# SCH_HVACPCBProject_2026-05-03.net
KiCad netlist of a schematic drawn in EasyEDA
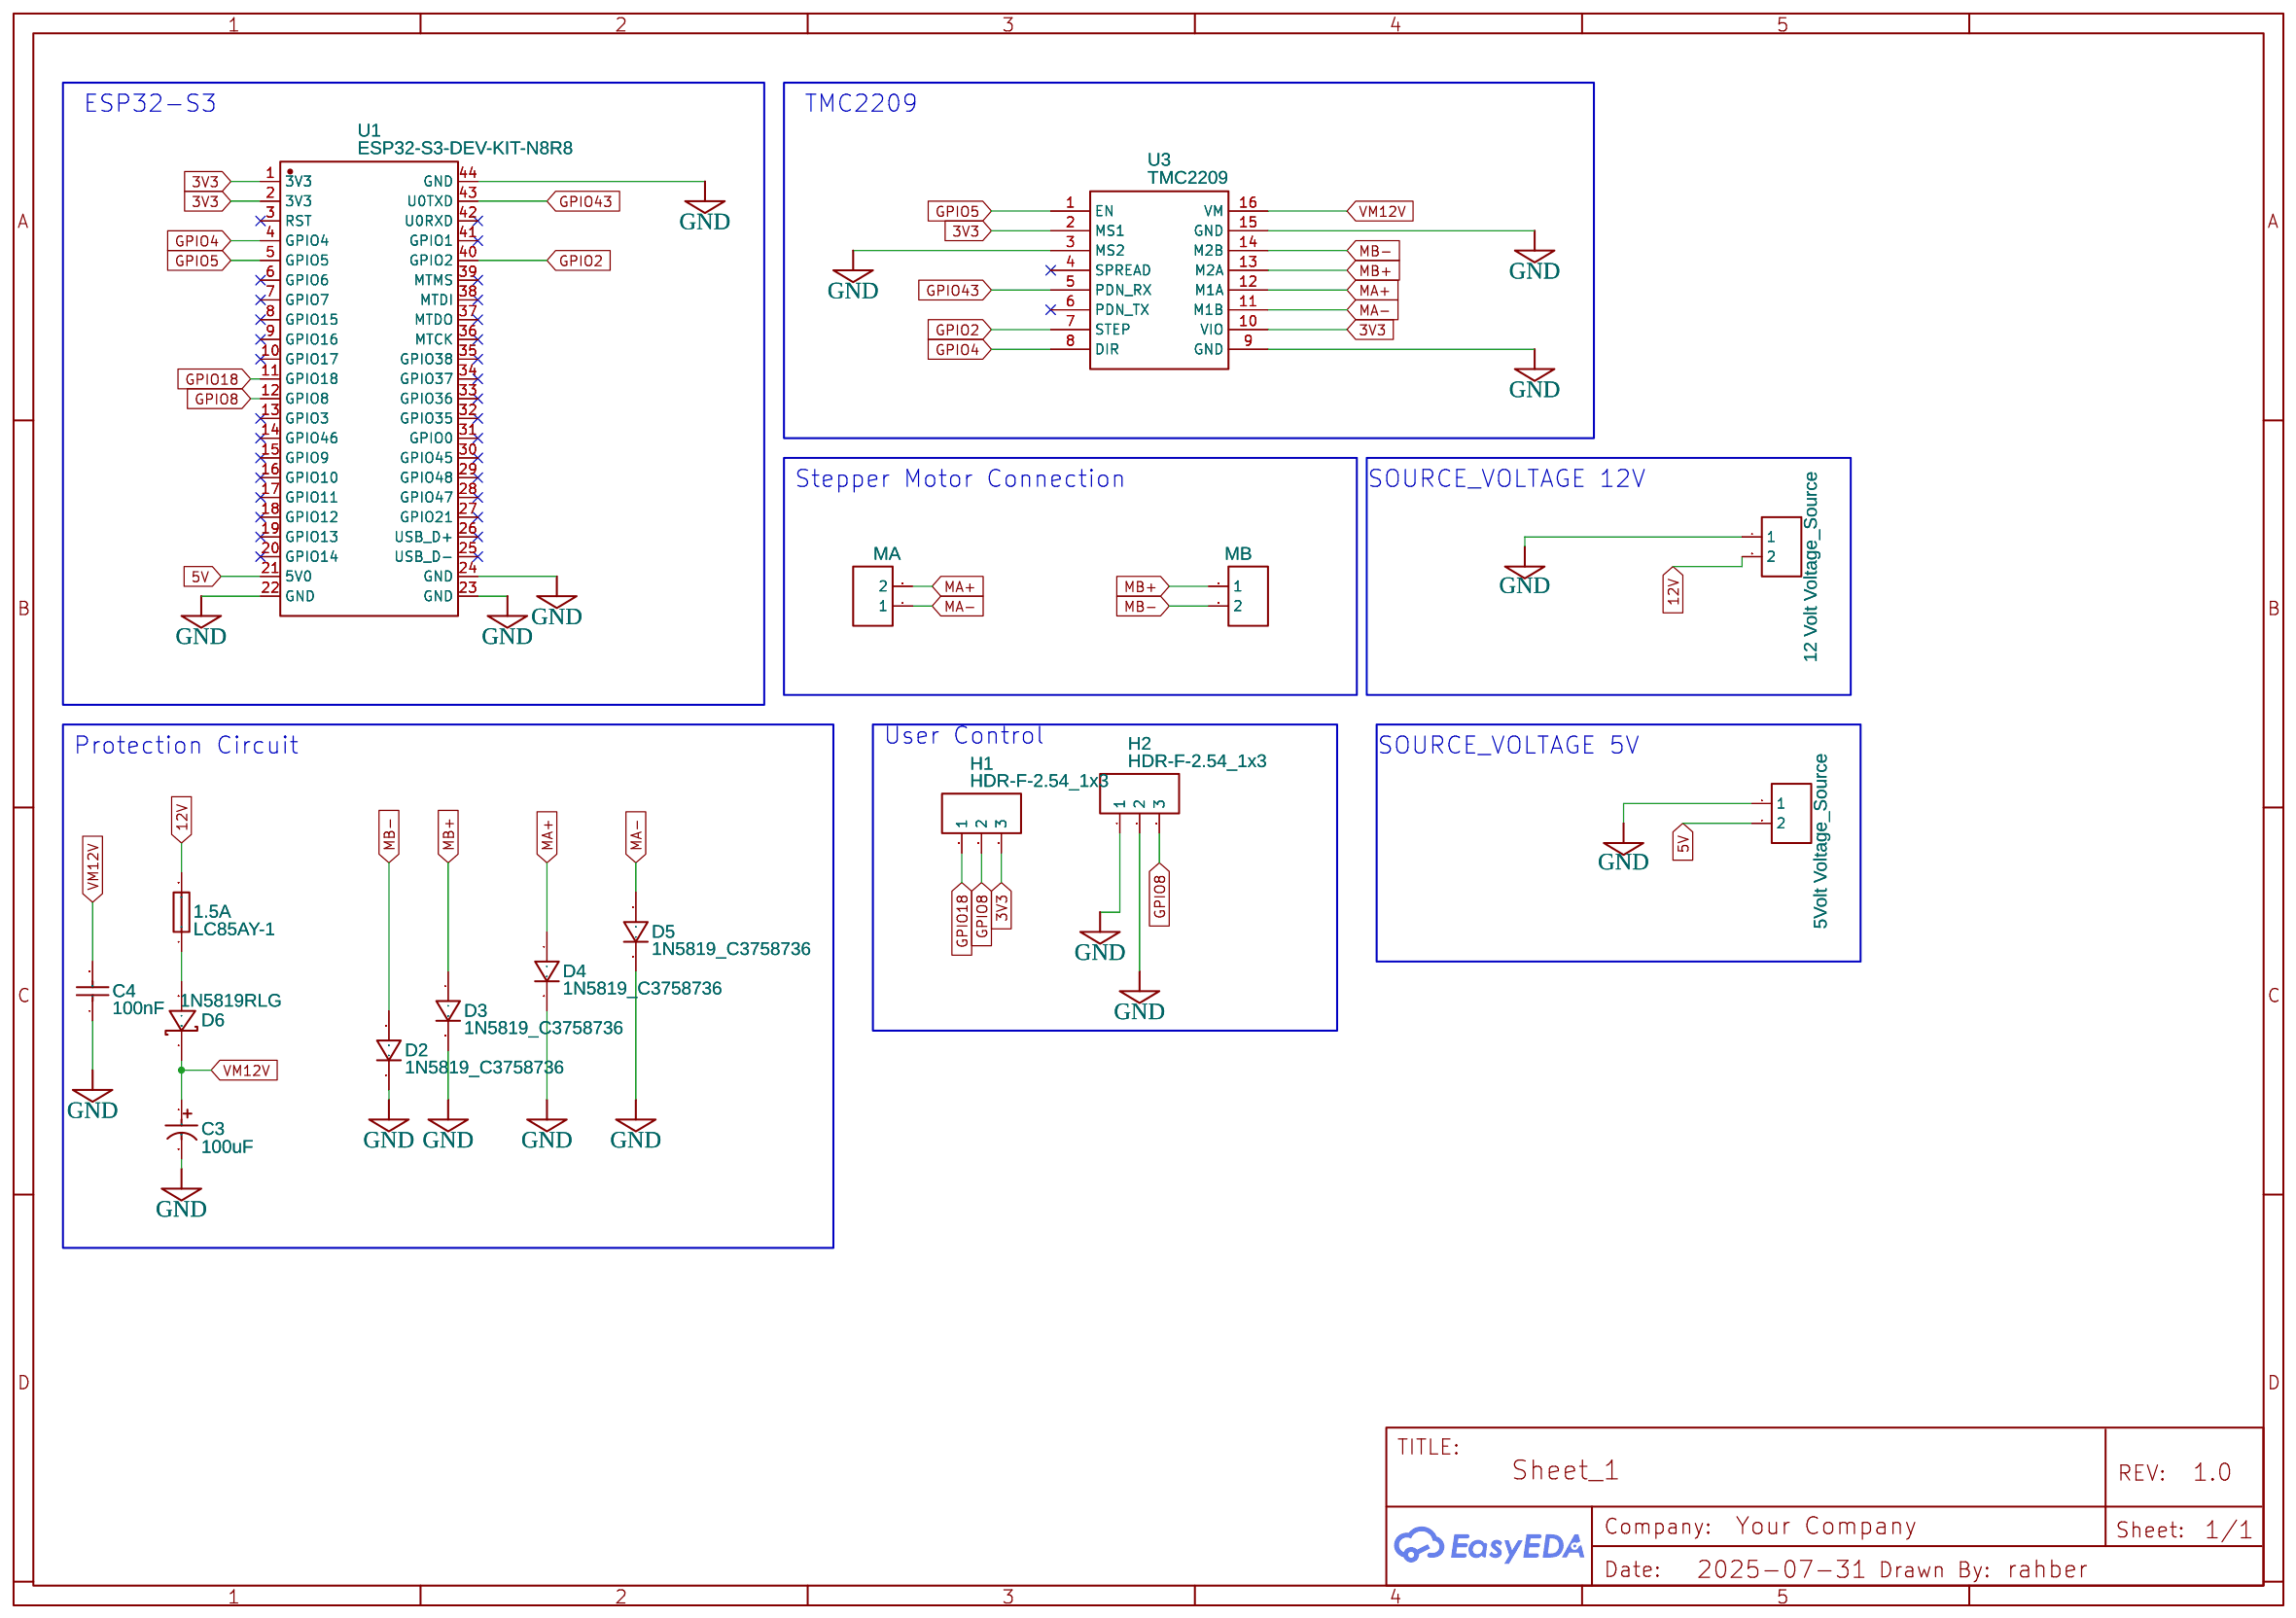
[diagram p0: schematic sheet]

(export (version "E")
  (design (tool "Eeschema 10.0.6"))
  (components
    (comp (ref "1.5A")
      (value "LC85AY-1")
      (fields (field (name "Manufacturer") "BOURNS"))
      (libsource (lib "") (part "LC85AY-1"))
    )
    (comp (ref "C3")
      (value "100uF")
      (fields
        (field (name "Manufacturer Part") "NP106V100G12RR0VH2FP0")
        (field (name "Manufacturer") "CX(承兴)")
      )
      (libsource (lib "") (part "Non - polar electrolytic capacitors10uf 100v"))
    )
    (comp (ref "C4")
      (value "100nF")
      (fields (field (name "Manufacturer Part") "瓷片电容47PF 3KV"))
      (libsource (lib "") (part "Ceramic capacitors47PF 3KV"))
    )
    (comp (ref "D2")
      (value "1N5819_C3758736")
      (fields
        (field (name "Manufacturer Part") "1N5819")
        (field (name "Manufacturer") "Taiwan Semiconductor(台湾半导体)")
      )
      (libsource (lib "") (part "1N5819_C3758736"))
    )
    (comp (ref "D3")
      (value "1N5819_C3758736")
      (fields
        (field (name "Manufacturer Part") "1N5819")
        (field (name "Manufacturer") "Taiwan Semiconductor(台湾半导体)")
      )
      (libsource (lib "") (part "1N5819_C3758736"))
    )
    (comp (ref "D4")
      (value "1N5819_C3758736")
      (fields
        (field (name "Manufacturer Part") "1N5819")
        (field (name "Manufacturer") "Taiwan Semiconductor(台湾半导体)")
      )
      (libsource (lib "") (part "1N5819_C3758736"))
    )
    (comp (ref "D5")
      (value "1N5819_C3758736")
      (fields
        (field (name "Manufacturer Part") "1N5819")
        (field (name "Manufacturer") "Taiwan Semiconductor(台湾半导体)")
      )
      (libsource (lib "") (part "1N5819_C3758736"))
    )
    (comp (ref "D6")
      (value "1N5819RLG")
      (fields (field (name "Manufacturer") "onsemi(安森美)"))
      (libsource (lib "") (part "1N5819RLG"))
    )
    (comp (ref "H1") (value "HDR-F-2.54_1x3") (libsource (lib "") (part "HDR-F-2.54_1x3")))
    (comp (ref "H2") (value "HDR-F-2.54_1x3") (libsource (lib "") (part "HDR-F-2.54_1x3")))
    (comp (ref "P1") (value "MB") (libsource (lib "") (part "CONN-TH_2P-P5.08")))
    (comp (ref "P2") (value "MA") (libsource (lib "") (part "CONN-TH_2P-P5.08_1")))
    (comp (ref "P3") (value "12 Volt Voltage_Source") (libsource (lib "") (part "CONN-TH_2P-P5.08")))
    (comp (ref "P5") (value "5Volt Voltage_Source") (libsource (lib "") (part "CONN-TH_2P-P5.08")))
    (comp (ref "U1") (value "ESP32-S3-DEV-KIT-N8R8") (libsource (lib "") (part "ESP32-S3-DEV-KIT-N8R8")))
    (comp (ref "U3") (value "TMC2209") (libsource (lib "") (part "TMC2209")))
  )
  (nets
    (net (code "1") (name "3V3") (class "Default")
      (node (ref "H1") (pin "3") (pinfunction "3_3") (pintype "input"))
      (node (ref "U1") (pin "1") (pinfunction "3V3_1") (pintype "unspecified"))
      (node (ref "U1") (pin "2") (pinfunction "3V3_2") (pintype "unspecified"))
      (node (ref "U3") (pin "10") (pinfunction "VIO_10") (pintype "unspecified"))
      (node (ref "U3") (pin "2") (pinfunction "MS1_2") (pintype "unspecified"))
    )
    (net (code "2") (name "5V") (class "Default")
      (node (ref "P5") (pin "2") (pinfunction "2_2") (pintype "unspecified"))
      (node (ref "U1") (pin "21") (pinfunction "5V0_21") (pintype "unspecified"))
    )
    (net (code "3") (name "12V") (class "Default")
      (node (ref "1.5A") (pin "2") (pinfunction "2_2") (pintype "unspecified"))
      (node (ref "P3") (pin "2") (pinfunction "2_2") (pintype "unspecified"))
    )
    (net (code "4") (name "GND") (class "Default")
      (node (ref "C3") (pin "2") (pinfunction "2_2") (pintype "input"))
      (node (ref "C4") (pin "1") (pinfunction "1_1") (pintype "input"))
      (node (ref "D2") (pin "2") (pinfunction "K_2") (pintype "unspecified"))
      (node (ref "D3") (pin "2") (pinfunction "K_2") (pintype "unspecified"))
      (node (ref "D4") (pin "2") (pinfunction "K_2") (pintype "unspecified"))
      (node (ref "D5") (pin "2") (pinfunction "K_2") (pintype "unspecified"))
      (node (ref "H2") (pin "1") (pinfunction "1_1") (pintype "input"))
      (node (ref "H2") (pin "2") (pinfunction "2_2") (pintype "input"))
      (node (ref "P3") (pin "1") (pinfunction "1_1") (pintype "unspecified"))
      (node (ref "P5") (pin "1") (pinfunction "1_1") (pintype "unspecified"))
      (node (ref "U1") (pin "22") (pinfunction "GND_22") (pintype "unspecified"))
      (node (ref "U1") (pin "23") (pinfunction "GND_23") (pintype "unspecified"))
      (node (ref "U1") (pin "24") (pinfunction "GND_24") (pintype "unspecified"))
      (node (ref "U1") (pin "44") (pinfunction "GND_44") (pintype "unspecified"))
      (node (ref "U3") (pin "15") (pinfunction "GND_15") (pintype "unspecified"))
      (node (ref "U3") (pin "3") (pinfunction "MS2_3") (pintype "unspecified"))
      (node (ref "U3") (pin "9") (pinfunction "GND_9") (pintype "unspecified"))
    )
    (net (code "5") (name "GPIO2") (class "Default")
      (node (ref "U1") (pin "40") (pinfunction "GPIO2_40") (pintype "unspecified"))
      (node (ref "U3") (pin "7") (pinfunction "STEP_7") (pintype "unspecified"))
    )
    (net (code "6") (name "GPIO4") (class "Default")
      (node (ref "U1") (pin "4") (pinfunction "GPIO4_4") (pintype "unspecified"))
      (node (ref "U3") (pin "8") (pinfunction "DIR_8") (pintype "unspecified"))
    )
    (net (code "7") (name "GPIO5") (class "Default")
      (node (ref "U1") (pin "5") (pinfunction "GPIO5_5") (pintype "unspecified"))
      (node (ref "U3") (pin "1") (pinfunction "EN_1") (pintype "unspecified"))
    )
    (net (code "8") (name "GPIO8") (class "Default")
      (node (ref "H1") (pin "2") (pinfunction "2_2") (pintype "input"))
      (node (ref "H2") (pin "3") (pinfunction "3_3") (pintype "input"))
      (node (ref "U1") (pin "12") (pinfunction "GPIO8_12") (pintype "unspecified"))
    )
    (net (code "9") (name "GPIO18") (class "Default")
      (node (ref "H1") (pin "1") (pinfunction "1_1") (pintype "input"))
      (node (ref "U1") (pin "11") (pinfunction "GPIO18_11") (pintype "unspecified"))
    )
    (net (code "10") (name "GPIO43") (class "Default")
      (node (ref "U1") (pin "43") (pinfunction "U0TXD_43") (pintype "unspecified"))
      (node (ref "U3") (pin "5") (pinfunction "PDN_RX_5") (pintype "unspecified"))
    )
    (net (code "11") (name "MA+") (class "Default")
      (node (ref "D4") (pin "1") (pinfunction "A_1") (pintype "unspecified"))
      (node (ref "P2") (pin "2") (pinfunction "2_2") (pintype "unspecified"))
      (node (ref "U3") (pin "12") (pinfunction "M1A_12") (pintype "unspecified"))
    )
    (net (code "12") (name "MA-") (class "Default")
      (node (ref "D5") (pin "1") (pinfunction "A_1") (pintype "unspecified"))
      (node (ref "P2") (pin "1") (pinfunction "1_1") (pintype "unspecified"))
      (node (ref "U3") (pin "11") (pinfunction "M1B_11") (pintype "unspecified"))
    )
    (net (code "13") (name "MB+") (class "Default")
      (node (ref "D3") (pin "1") (pinfunction "A_1") (pintype "unspecified"))
      (node (ref "P1") (pin "1") (pinfunction "1_1") (pintype "unspecified"))
      (node (ref "U3") (pin "13") (pinfunction "M2A_13") (pintype "unspecified"))
    )
    (net (code "14") (name "MB-") (class "Default")
      (node (ref "D2") (pin "1") (pinfunction "A_1") (pintype "unspecified"))
      (node (ref "P1") (pin "2") (pinfunction "2_2") (pintype "unspecified"))
      (node (ref "U3") (pin "14") (pinfunction "M2B_14") (pintype "unspecified"))
    )
    (net (code "15") (name "Net-(D6-A)") (class "Default")
      (node (ref "1.5A") (pin "1") (pinfunction "1_1") (pintype "unspecified"))
      (node (ref "D6") (pin "2") (pinfunction "A_2") (pintype "unspecified"))
    )
    (net (code "16") (name "VM12V") (class "Default")
      (node (ref "C3") (pin "1") (pinfunction "1_1") (pintype "input"))
      (node (ref "C4") (pin "2") (pinfunction "2_2") (pintype "input"))
      (node (ref "D6") (pin "1") (pinfunction "C_1") (pintype "unspecified"))
      (node (ref "U3") (pin "16") (pinfunction "VM_16") (pintype "unspecified"))
    )
    (net (code "17") (name "unconnected-(U1-GPIO0-Pad31)") (class "Default")
      (node (ref "U1") (pin "31") (pinfunction "GPIO0_31") (pintype "unspecified+no_connect"))
    )
    (net (code "18") (name "unconnected-(U1-GPIO1-Pad41)") (class "Default")
      (node (ref "U1") (pin "41") (pinfunction "GPIO1_41") (pintype "unspecified+no_connect"))
    )
    (net (code "19") (name "unconnected-(U1-GPIO3-Pad13)") (class "Default")
      (node (ref "U1") (pin "13") (pinfunction "GPIO3_13") (pintype "unspecified+no_connect"))
    )
    (net (code "20") (name "unconnected-(U1-GPIO6-Pad6)") (class "Default")
      (node (ref "U1") (pin "6") (pinfunction "GPIO6_6") (pintype "unspecified+no_connect"))
    )
    (net (code "21") (name "unconnected-(U1-GPIO7-Pad7)") (class "Default")
      (node (ref "U1") (pin "7") (pinfunction "GPIO7_7") (pintype "unspecified+no_connect"))
    )
    (net (code "22") (name "unconnected-(U1-GPIO9-Pad15)") (class "Default")
      (node (ref "U1") (pin "15") (pinfunction "GPIO9_15") (pintype "unspecified+no_connect"))
    )
    (net (code "23") (name "unconnected-(U1-GPIO10-Pad16)") (class "Default")
      (node (ref "U1") (pin "16") (pinfunction "GPIO10_16") (pintype "unspecified+no_connect"))
    )
    (net (code "24") (name "unconnected-(U1-GPIO11-Pad17)") (class "Default")
      (node (ref "U1") (pin "17") (pinfunction "GPIO11_17") (pintype "unspecified+no_connect"))
    )
    (net (code "25") (name "unconnected-(U1-GPIO12-Pad18)") (class "Default")
      (node (ref "U1") (pin "18") (pinfunction "GPIO12_18") (pintype "unspecified+no_connect"))
    )
    (net (code "26") (name "unconnected-(U1-GPIO13-Pad19)") (class "Default")
      (node (ref "U1") (pin "19") (pinfunction "GPIO13_19") (pintype "unspecified+no_connect"))
    )
    (net (code "27") (name "unconnected-(U1-GPIO14-Pad20)") (class "Default")
      (node (ref "U1") (pin "20") (pinfunction "GPIO14_20") (pintype "unspecified+no_connect"))
    )
    (net (code "28") (name "unconnected-(U1-GPIO15-Pad8)") (class "Default")
      (node (ref "U1") (pin "8") (pinfunction "GPIO15_8") (pintype "unspecified+no_connect"))
    )
    (net (code "29") (name "unconnected-(U1-GPIO16-Pad9)") (class "Default")
      (node (ref "U1") (pin "9") (pinfunction "GPIO16_9") (pintype "unspecified+no_connect"))
    )
    (net (code "30") (name "unconnected-(U1-GPIO17-Pad10)") (class "Default")
      (node (ref "U1") (pin "10") (pinfunction "GPIO17_10") (pintype "unspecified+no_connect"))
    )
    (net (code "31") (name "unconnected-(U1-GPIO21-Pad27)") (class "Default")
      (node (ref "U1") (pin "27") (pinfunction "GPIO21_27") (pintype "unspecified+no_connect"))
    )
    (net (code "32") (name "unconnected-(U1-GPIO35-Pad32)") (class "Default")
      (node (ref "U1") (pin "32") (pinfunction "GPIO35_32") (pintype "unspecified+no_connect"))
    )
    (net (code "33") (name "unconnected-(U1-GPIO36-Pad33)") (class "Default")
      (node (ref "U1") (pin "33") (pinfunction "GPIO36_33") (pintype "unspecified+no_connect"))
    )
    (net (code "34") (name "unconnected-(U1-GPIO37-Pad34)") (class "Default")
      (node (ref "U1") (pin "34") (pinfunction "GPIO37_34") (pintype "unspecified+no_connect"))
    )
    (net (code "35") (name "unconnected-(U1-GPIO38-Pad35)") (class "Default")
      (node (ref "U1") (pin "35") (pinfunction "GPIO38_35") (pintype "unspecified+no_connect"))
    )
    (net (code "36") (name "unconnected-(U1-GPIO45-Pad30)") (class "Default")
      (node (ref "U1") (pin "30") (pinfunction "GPIO45_30") (pintype "unspecified+no_connect"))
    )
    (net (code "37") (name "unconnected-(U1-GPIO46-Pad14)") (class "Default")
      (node (ref "U1") (pin "14") (pinfunction "GPIO46_14") (pintype "unspecified+no_connect"))
    )
    (net (code "38") (name "unconnected-(U1-GPIO47-Pad28)") (class "Default")
      (node (ref "U1") (pin "28") (pinfunction "GPIO47_28") (pintype "unspecified+no_connect"))
    )
    (net (code "39") (name "unconnected-(U1-GPIO48-Pad29)") (class "Default")
      (node (ref "U1") (pin "29") (pinfunction "GPIO48_29") (pintype "unspecified+no_connect"))
    )
    (net (code "40") (name "unconnected-(U1-MTCK-Pad36)") (class "Default")
      (node (ref "U1") (pin "36") (pinfunction "MTCK_36") (pintype "unspecified+no_connect"))
    )
    (net (code "41") (name "unconnected-(U1-MTDI-Pad38)") (class "Default")
      (node (ref "U1") (pin "38") (pinfunction "MTDI_38") (pintype "unspecified+no_connect"))
    )
    (net (code "42") (name "unconnected-(U1-MTDO-Pad37)") (class "Default")
      (node (ref "U1") (pin "37") (pinfunction "MTDO_37") (pintype "unspecified+no_connect"))
    )
    (net (code "43") (name "unconnected-(U1-MTMS-Pad39)") (class "Default")
      (node (ref "U1") (pin "39") (pinfunction "MTMS_39") (pintype "unspecified+no_connect"))
    )
    (net (code "44") (name "unconnected-(U1-RST-Pad3)") (class "Default")
      (node (ref "U1") (pin "3") (pinfunction "RST_3") (pintype "unspecified+no_connect"))
    )
    (net (code "45") (name "unconnected-(U1-U0RXD-Pad42)") (class "Default")
      (node (ref "U1") (pin "42") (pinfunction "U0RXD_42") (pintype "unspecified+no_connect"))
    )
    (net (code "46") (name "unconnected-(U1-USB_D+-Pad26)") (class "Default")
      (node (ref "U1") (pin "26") (pinfunction "USB_D+_26") (pintype "unspecified+no_connect"))
    )
    (net (code "47") (name "unconnected-(U1-USB_D--Pad25)") (class "Default")
      (node (ref "U1") (pin "25") (pinfunction "USB_D-_25") (pintype "unspecified+no_connect"))
    )
    (net (code "48") (name "unconnected-(U3-PDN_TX-Pad6)") (class "Default")
      (node (ref "U3") (pin "6") (pinfunction "PDN_TX_6") (pintype "unspecified+no_connect"))
    )
    (net (code "49") (name "unconnected-(U3-SPREAD-Pad4)") (class "Default")
      (node (ref "U3") (pin "4") (pinfunction "SPREAD_4") (pintype "unspecified+no_connect"))
    )
  )
)
